# Main_circuit.net
KiCad netlist of a schematic drawn in Altium Designer
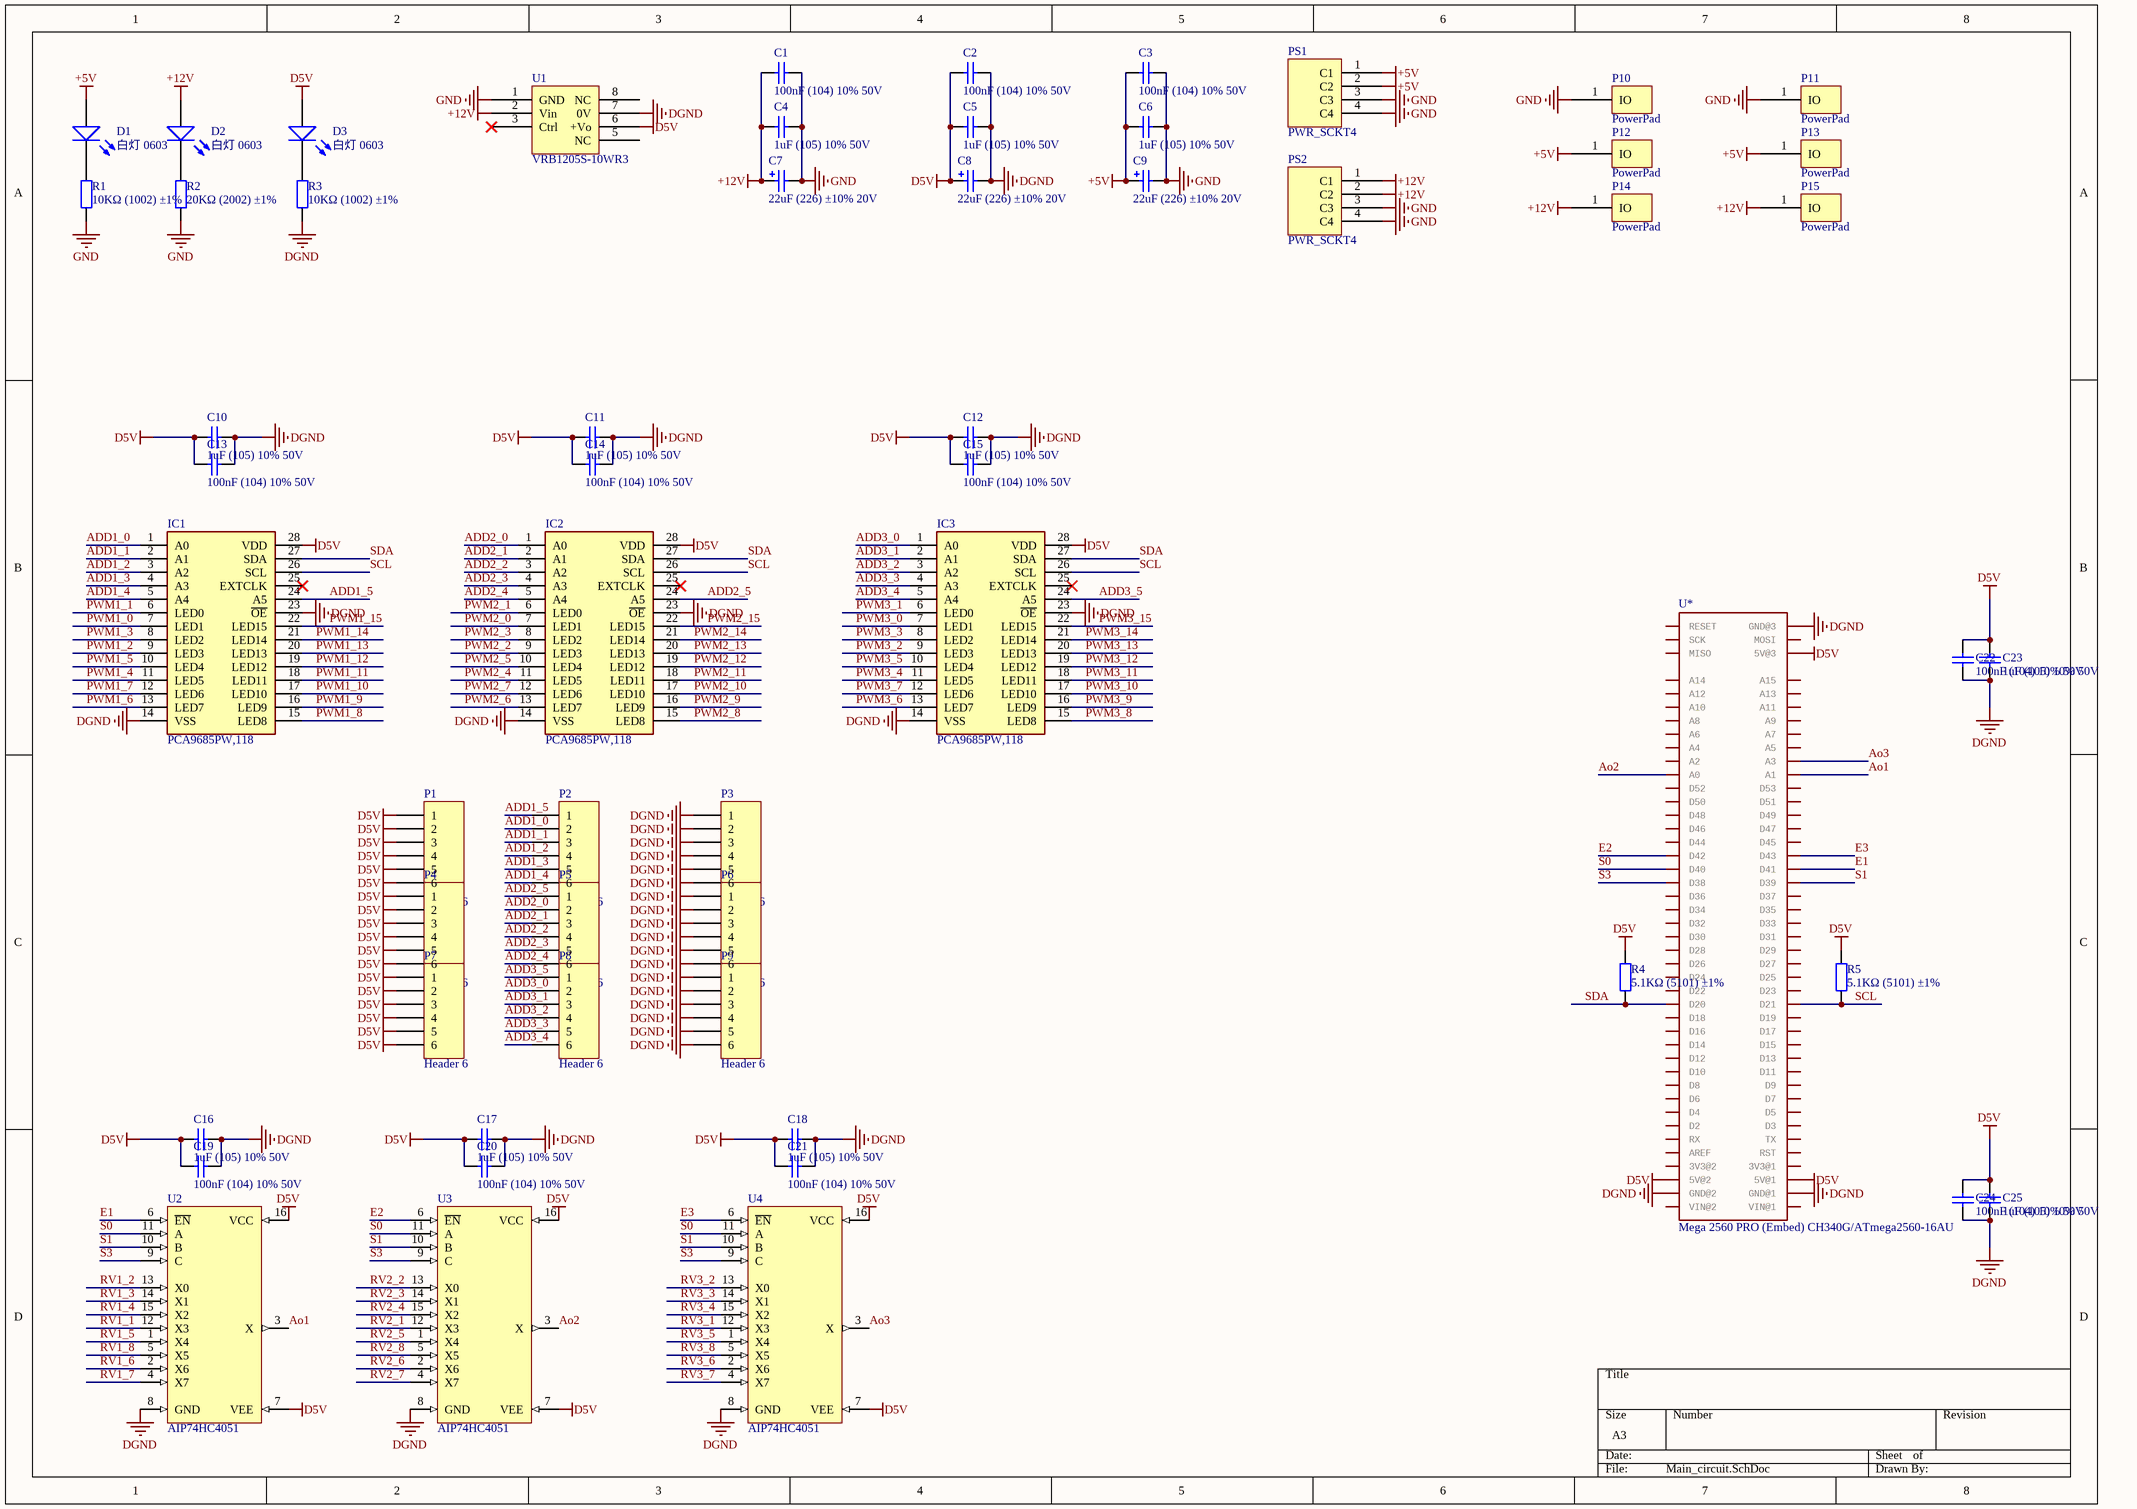
[diagram p0: Main_circuit.SchDoc]

(export (version "E")
  (design (tool "Eeschema 10.0.6"))
  (components
    (comp (ref "C1")
      (value "100nF (104) 10% 50V")
      (footprint "LC-0603_C")
      (description "贴片电容")
      (libsource (lib "Miscellaneous Devices LC") (part "0603 100nF (104) 10% 50V"))
    )
    (comp (ref "C2")
      (value "100nF (104) 10% 50V")
      (footprint "LC-0603_C")
      (description "贴片电容")
      (libsource (lib "Miscellaneous Devices LC") (part "0603 100nF (104) 10% 50V"))
    )
    (comp (ref "C3")
      (value "100nF (104) 10% 50V")
      (footprint "LC-0603_C")
      (description "贴片电容")
      (libsource (lib "Miscellaneous Devices LC") (part "0603 100nF (104) 10% 50V"))
    )
    (comp (ref "C4")
      (value "1uF (105) 10% 50V")
      (footprint "LC-0603_C")
      (description "贴片电容")
      (libsource (lib "Miscellaneous Devices LC") (part "0603 1uF (105) 10% 50V"))
    )
    (comp (ref "C5")
      (value "1uF (105) 10% 50V")
      (footprint "LC-0603_C")
      (description "贴片电容")
      (libsource (lib "Miscellaneous Devices LC") (part "0603 1uF (105) 10% 50V"))
    )
    (comp (ref "C6")
      (value "1uF (105) 10% 50V")
      (footprint "LC-0603_C")
      (description "贴片电容")
      (libsource (lib "Miscellaneous Devices LC") (part "0603 1uF (105) 10% 50V"))
    )
    (comp (ref "C7")
      (value "22uF (226) ±10% 20V")
      (footprint "LC-CASE-B_3528")
      (description "钽电容")
      (libsource (lib "Miscellaneous Devices LC") (part "3216 10uF (106) 10% 16V"))
    )
    (comp (ref "C8")
      (value "22uF (226) ±10% 20V")
      (footprint "LC-CASE-B_3528")
      (description "钽电容")
      (libsource (lib "Miscellaneous Devices LC") (part "3216 10uF (106) 10% 16V"))
    )
    (comp (ref "C9")
      (value "22uF (226) ±10% 20V")
      (footprint "LC-CASE-B_3528")
      (description "钽电容")
      (libsource (lib "Miscellaneous Devices LC") (part "3216 10uF (106) 10% 16V"))
    )
    (comp (ref "C10")
      (value "1uF (105) 10% 50V")
      (footprint "LC-0603_C")
      (description "贴片电容")
      (libsource (lib "Miscellaneous Devices LC") (part "0603 1uF (105) 10% 50V"))
    )
    (comp (ref "C11")
      (value "1uF (105) 10% 50V")
      (footprint "LC-0603_C")
      (description "贴片电容")
      (libsource (lib "Miscellaneous Devices LC") (part "0603 1uF (105) 10% 50V"))
    )
    (comp (ref "C12")
      (value "1uF (105) 10% 50V")
      (footprint "LC-0603_C")
      (description "贴片电容")
      (libsource (lib "Miscellaneous Devices LC") (part "0603 1uF (105) 10% 50V"))
    )
    (comp (ref "C13")
      (value "100nF (104) 10% 50V")
      (footprint "LC-0603_C")
      (description "贴片电容")
      (libsource (lib "Miscellaneous Devices LC") (part "0603 100nF (104) 10% 50V"))
    )
    (comp (ref "C14")
      (value "100nF (104) 10% 50V")
      (footprint "LC-0603_C")
      (description "贴片电容")
      (libsource (lib "Miscellaneous Devices LC") (part "0603 100nF (104) 10% 50V"))
    )
    (comp (ref "C15")
      (value "100nF (104) 10% 50V")
      (footprint "LC-0603_C")
      (description "贴片电容")
      (libsource (lib "Miscellaneous Devices LC") (part "0603 100nF (104) 10% 50V"))
    )
    (comp (ref "C16")
      (value "1uF (105) 10% 50V")
      (footprint "LC-0603_C")
      (description "贴片电容")
      (libsource (lib "Miscellaneous Devices LC") (part "0603 1uF (105) 10% 50V"))
    )
    (comp (ref "C17")
      (value "1uF (105) 10% 50V")
      (footprint "LC-0603_C")
      (description "贴片电容")
      (libsource (lib "Miscellaneous Devices LC") (part "0603 1uF (105) 10% 50V"))
    )
    (comp (ref "C18")
      (value "1uF (105) 10% 50V")
      (footprint "LC-0603_C")
      (description "贴片电容")
      (libsource (lib "Miscellaneous Devices LC") (part "0603 1uF (105) 10% 50V"))
    )
    (comp (ref "C19")
      (value "100nF (104) 10% 50V")
      (footprint "LC-0603_C")
      (description "贴片电容")
      (libsource (lib "Miscellaneous Devices LC") (part "0603 100nF (104) 10% 50V"))
    )
    (comp (ref "C20")
      (value "100nF (104) 10% 50V")
      (footprint "LC-0603_C")
      (description "贴片电容")
      (libsource (lib "Miscellaneous Devices LC") (part "0603 100nF (104) 10% 50V"))
    )
    (comp (ref "C21")
      (value "100nF (104) 10% 50V")
      (footprint "LC-0603_C")
      (description "贴片电容")
      (libsource (lib "Miscellaneous Devices LC") (part "0603 100nF (104) 10% 50V"))
    )
    (comp (ref "C22")
      (value "100nF (104) 10% 50V")
      (footprint "LC-0603_C")
      (description "贴片电容")
      (libsource (lib "Miscellaneous Devices LC") (part "0603 100nF (104) 10% 50V"))
    )
    (comp (ref "C23")
      (value "1uF (105) 10% 50V")
      (footprint "LC-0603_C")
      (description "贴片电容")
      (libsource (lib "Miscellaneous Devices LC") (part "0603 1uF (105) 10% 50V"))
    )
    (comp (ref "C24")
      (value "100nF (104) 10% 50V")
      (footprint "LC-0603_C")
      (description "贴片电容")
      (libsource (lib "Miscellaneous Devices LC") (part "0603 100nF (104) 10% 50V"))
    )
    (comp (ref "C25")
      (value "1uF (105) 10% 50V")
      (footprint "LC-0603_C")
      (description "贴片电容")
      (libsource (lib "Miscellaneous Devices LC") (part "0603 1uF (105) 10% 50V"))
    )
    (comp (ref "D1")
      (value "白灯 0603")
      (footprint "LC-0603_LED_S1")
      (description "发光二极管")
      (libsource (lib "Miscellaneous Devices LC") (part "0603 白灯"))
    )
    (comp (ref "D2")
      (value "白灯 0603")
      (footprint "LC-0603_LED_S1")
      (description "发光二极管")
      (libsource (lib "Miscellaneous Devices LC") (part "0603 白灯"))
    )
    (comp (ref "D3")
      (value "白灯 0603")
      (footprint "LC-0603_LED_S1")
      (description "发光二极管")
      (libsource (lib "Miscellaneous Devices LC") (part "0603 白灯"))
    )
    (comp (ref "IC1")
      (value "PCA9685PW,118")
      (footprint "LC-TSSOP-28")
      (description "Integrated Circuit")
      (libsource (lib "*") (part "PCA9685PW,118"))
    )
    (comp (ref "IC2")
      (value "PCA9685PW,118")
      (footprint "LC-TSSOP-28")
      (description "Integrated Circuit")
      (libsource (lib "*") (part "PCA9685PW,118"))
    )
    (comp (ref "IC3")
      (value "PCA9685PW,118")
      (footprint "LC-TSSOP-28")
      (description "Integrated Circuit")
      (libsource (lib "*") (part "PCA9685PW,118"))
    )
    (comp (ref "P1")
      (value "Header 6")
      (footprint "HDR1X6")
      (description "Header, 6-Pin")
      (fields (field (name "PUBLISHER") "Altium Limited"))
      (libsource (lib "Miscellaneous Connectors") (part "Header 6"))
    )
    (comp (ref "P2")
      (value "Header 6")
      (footprint "HDR1X6")
      (description "Header, 6-Pin")
      (fields (field (name "PUBLISHER") "Altium Limited"))
      (libsource (lib "Miscellaneous Connectors") (part "Header 6"))
    )
    (comp (ref "P3")
      (value "Header 6")
      (footprint "HDR1X6")
      (description "Header, 6-Pin")
      (fields (field (name "PUBLISHER") "Altium Limited"))
      (libsource (lib "Miscellaneous Connectors") (part "Header 6"))
    )
    (comp (ref "P4")
      (value "Header 6")
      (footprint "HDR1X6")
      (description "Header, 6-Pin")
      (fields (field (name "PUBLISHER") "Altium Limited"))
      (libsource (lib "Miscellaneous Connectors") (part "Header 6"))
    )
    (comp (ref "P5")
      (value "Header 6")
      (footprint "HDR1X6")
      (description "Header, 6-Pin")
      (fields (field (name "PUBLISHER") "Altium Limited"))
      (libsource (lib "Miscellaneous Connectors") (part "Header 6"))
    )
    (comp (ref "P6")
      (value "Header 6")
      (footprint "HDR1X6")
      (description "Header, 6-Pin")
      (fields (field (name "PUBLISHER") "Altium Limited"))
      (libsource (lib "Miscellaneous Connectors") (part "Header 6"))
    )
    (comp (ref "P7")
      (value "Header 6")
      (footprint "HDR1X6")
      (description "Header, 6-Pin")
      (fields (field (name "PUBLISHER") "Altium Limited"))
      (libsource (lib "Miscellaneous Connectors") (part "Header 6"))
    )
    (comp (ref "P8")
      (value "Header 6")
      (footprint "HDR1X6")
      (description "Header, 6-Pin")
      (fields (field (name "PUBLISHER") "Altium Limited"))
      (libsource (lib "Miscellaneous Connectors") (part "Header 6"))
    )
    (comp (ref "P9")
      (value "Header 6")
      (footprint "HDR1X6")
      (description "Header, 6-Pin")
      (fields (field (name "PUBLISHER") "Altium Limited"))
      (libsource (lib "Miscellaneous Connectors") (part "Header 6"))
    )
    (comp (ref "P10") (value "PowerPad") (footprint "PowerPad") (libsource (lib "Schlib1") (part "PowerPad")))
    (comp (ref "P11") (value "PowerPad") (footprint "PowerPad") (libsource (lib "Schlib1") (part "PowerPad")))
    (comp (ref "P12") (value "PowerPad") (footprint "PowerPad") (libsource (lib "Schlib1") (part "PowerPad")))
    (comp (ref "P13") (value "PowerPad") (footprint "PowerPad") (libsource (lib "Schlib1") (part "PowerPad")))
    (comp (ref "P14") (value "PowerPad") (footprint "PowerPad") (libsource (lib "Schlib1") (part "PowerPad")))
    (comp (ref "P15") (value "PowerPad") (footprint "PowerPad") (libsource (lib "Schlib1") (part "PowerPad")))
    (comp (ref "PS1")
      (value "PWR_SCKT4")
      (footprint "PWR_SCKT_4P3.81")
      (description "POWER SOCKET")
      (libsource (lib "PG_lib") (part "POWER_SOCKET4"))
    )
    (comp (ref "PS2")
      (value "PWR_SCKT4")
      (footprint "PWR_SCKT_4P3.81")
      (description "POWER SOCKET")
      (libsource (lib "PG_lib") (part "POWER_SOCKET4"))
    )
    (comp (ref "R1")
      (value "10KΩ (1002) ±1%")
      (footprint "LC-0603_R")
      (description "贴片电阻")
      (libsource (lib "Miscellaneous Devices LC") (part "0603 10KΩ (1002) 1%"))
    )
    (comp (ref "R2")
      (value "20KΩ (2002) ±1%")
      (footprint "LC-0603_R")
      (description "贴片电阻")
      (libsource (lib "Miscellaneous Devices LC") (part "0603 20KΩ (2002) 1%"))
    )
    (comp (ref "R3")
      (value "10KΩ (1002) ±1%")
      (footprint "LC-0603_R")
      (description "贴片电阻")
      (libsource (lib "Miscellaneous Devices LC") (part "0603 10KΩ (1002) 1%"))
    )
    (comp (ref "R4")
      (value "5.1KΩ (5101) ±1%")
      (footprint "LC-0603_R")
      (description "贴片电阻")
      (libsource (lib "Miscellaneous Devices LC") (part "0603 5.1KΩ (5101) 1%"))
    )
    (comp (ref "R5")
      (value "5.1KΩ (5101) ±1%")
      (footprint "LC-0603_R")
      (description "贴片电阻")
      (libsource (lib "Miscellaneous Devices LC") (part "0603 5.1KΩ (5101) 1%"))
    )
    (comp (ref "U*")
      (value "Mega 2560 PRO (Embed) CH340G/ATmega2560-16AU")
      (footprint "Mega 2560 PRO (Embed)")
      (libsource (lib "Mega2560Pro") (part "Mega 2560 PRO (Embed)"))
    )
    (comp (ref "U1")
      (value "VRB1205S-10WR3")
      (footprint "VRB1205S-10WR3")
      (libsource (lib "Schlib1") (part "VRB1205S-10WR3"))
    )
    (comp (ref "U2")
      (value "AIP74HC4051")
      (footprint "LC-SOP-16_150mil")
      (description "4000系列逻辑芯片")
      (libsource (lib "Miscellaneous Devices LC") (part "CD4051BM96"))
    )
    (comp (ref "U3")
      (value "AIP74HC4051")
      (footprint "LC-SOP-16_150mil")
      (description "4000系列逻辑芯片")
      (libsource (lib "Miscellaneous Devices LC") (part "CD4051BM96"))
    )
    (comp (ref "U4")
      (value "AIP74HC4051")
      (footprint "LC-SOP-16_150mil")
      (description "4000系列逻辑芯片")
      (libsource (lib "Miscellaneous Devices LC") (part "CD4051BM96"))
    )
  )
  (nets
    (net (code "1") (name "+5V") (class "Default")
      (node (ref "C3") (pin "2") (pinfunction "2_2") (pintype "passive"))
      (node (ref "C6") (pin "2") (pinfunction "2_2") (pintype "passive"))
      (node (ref "C9") (pin "1") (pinfunction "1_1") (pintype "passive"))
      (node (ref "D1") (pin "A") (pinfunction "A_A") (pintype "passive"))
      (node (ref "P12") (pin "1") (pinfunction "IO_1") (pintype "passive"))
      (node (ref "P13") (pin "1") (pinfunction "IO_1") (pintype "passive"))
      (node (ref "PS1") (pin "1") (pinfunction "C1_1") (pintype "passive"))
      (node (ref "PS1") (pin "2") (pinfunction "C2_2") (pintype "passive"))
    )
    (net (code "2") (name "+12V") (class "Default")
      (node (ref "C1") (pin "2") (pinfunction "2_2") (pintype "passive"))
      (node (ref "C4") (pin "2") (pinfunction "2_2") (pintype "passive"))
      (node (ref "C7") (pin "1") (pinfunction "1_1") (pintype "passive"))
      (node (ref "D2") (pin "A") (pinfunction "A_A") (pintype "passive"))
      (node (ref "P14") (pin "1") (pinfunction "IO_1") (pintype "passive"))
      (node (ref "P15") (pin "1") (pinfunction "IO_1") (pintype "passive"))
      (node (ref "PS2") (pin "1") (pinfunction "C1_1") (pintype "passive"))
      (node (ref "PS2") (pin "2") (pinfunction "C2_2") (pintype "passive"))
      (node (ref "U1") (pin "2") (pinfunction "Vin_2") (pintype "passive"))
    )
    (net (code "3") (name "/ADD1_0") (class "Default")
      (node (ref "IC1") (pin "1") (pinfunction "A0_1") (pintype "passive"))
      (node (ref "P2") (pin "2") (pinfunction "2_2") (pintype "passive"))
    )
    (net (code "4") (name "/ADD1_1") (class "Default")
      (node (ref "IC1") (pin "2") (pinfunction "A1_2") (pintype "passive"))
      (node (ref "P2") (pin "3") (pinfunction "3_3") (pintype "passive"))
    )
    (net (code "5") (name "/ADD1_2") (class "Default")
      (node (ref "IC1") (pin "3") (pinfunction "A2_3") (pintype "passive"))
      (node (ref "P2") (pin "4") (pinfunction "4_4") (pintype "passive"))
    )
    (net (code "6") (name "/ADD1_3") (class "Default")
      (node (ref "IC1") (pin "4") (pinfunction "A3_4") (pintype "passive"))
      (node (ref "P2") (pin "5") (pinfunction "5_5") (pintype "passive"))
    )
    (net (code "7") (name "/ADD1_4") (class "Default")
      (node (ref "IC1") (pin "5") (pinfunction "A4_5") (pintype "passive"))
      (node (ref "P2") (pin "6") (pinfunction "6_6") (pintype "passive"))
    )
    (net (code "8") (name "/ADD1_5") (class "Default")
      (node (ref "IC1") (pin "24") (pinfunction "A5_24") (pintype "passive"))
      (node (ref "P2") (pin "1") (pinfunction "1_1") (pintype "passive"))
    )
    (net (code "9") (name "/ADD2_0") (class "Default")
      (node (ref "IC2") (pin "1") (pinfunction "A0_1") (pintype "passive"))
      (node (ref "P5") (pin "2") (pinfunction "2_2") (pintype "passive"))
    )
    (net (code "10") (name "/ADD2_1") (class "Default")
      (node (ref "IC2") (pin "2") (pinfunction "A1_2") (pintype "passive"))
      (node (ref "P5") (pin "3") (pinfunction "3_3") (pintype "passive"))
    )
    (net (code "11") (name "/ADD2_2") (class "Default")
      (node (ref "IC2") (pin "3") (pinfunction "A2_3") (pintype "passive"))
      (node (ref "P5") (pin "4") (pinfunction "4_4") (pintype "passive"))
    )
    (net (code "12") (name "/ADD2_3") (class "Default")
      (node (ref "IC2") (pin "4") (pinfunction "A3_4") (pintype "passive"))
      (node (ref "P5") (pin "5") (pinfunction "5_5") (pintype "passive"))
    )
    (net (code "13") (name "/ADD2_4") (class "Default")
      (node (ref "IC2") (pin "5") (pinfunction "A4_5") (pintype "passive"))
      (node (ref "P5") (pin "6") (pinfunction "6_6") (pintype "passive"))
    )
    (net (code "14") (name "/ADD2_5") (class "Default")
      (node (ref "IC2") (pin "24") (pinfunction "A5_24") (pintype "passive"))
      (node (ref "P5") (pin "1") (pinfunction "1_1") (pintype "passive"))
    )
    (net (code "15") (name "/ADD3_0") (class "Default")
      (node (ref "IC3") (pin "1") (pinfunction "A0_1") (pintype "passive"))
      (node (ref "P8") (pin "2") (pinfunction "2_2") (pintype "passive"))
    )
    (net (code "16") (name "/ADD3_1") (class "Default")
      (node (ref "IC3") (pin "2") (pinfunction "A1_2") (pintype "passive"))
      (node (ref "P8") (pin "3") (pinfunction "3_3") (pintype "passive"))
    )
    (net (code "17") (name "/ADD3_2") (class "Default")
      (node (ref "IC3") (pin "3") (pinfunction "A2_3") (pintype "passive"))
      (node (ref "P8") (pin "4") (pinfunction "4_4") (pintype "passive"))
    )
    (net (code "18") (name "/ADD3_3") (class "Default")
      (node (ref "IC3") (pin "4") (pinfunction "A3_4") (pintype "passive"))
      (node (ref "P8") (pin "5") (pinfunction "5_5") (pintype "passive"))
    )
    (net (code "19") (name "/ADD3_4") (class "Default")
      (node (ref "IC3") (pin "5") (pinfunction "A4_5") (pintype "passive"))
      (node (ref "P8") (pin "6") (pinfunction "6_6") (pintype "passive"))
    )
    (net (code "20") (name "/ADD3_5") (class "Default")
      (node (ref "IC3") (pin "24") (pinfunction "A5_24") (pintype "passive"))
      (node (ref "P8") (pin "1") (pinfunction "1_1") (pintype "passive"))
    )
    (net (code "21") (name "/Ao1") (class "Default")
      (node (ref "U*") (pin "A1") (pinfunction "A1_A1") (pintype "bidirectional"))
      (node (ref "U2") (pin "3") (pinfunction "X_3") (pintype "output"))
    )
    (net (code "22") (name "/Ao2") (class "Default")
      (node (ref "U*") (pin "A0") (pinfunction "A0_A0") (pintype "bidirectional"))
      (node (ref "U3") (pin "3") (pinfunction "X_3") (pintype "output"))
    )
    (net (code "23") (name "/Ao3") (class "Default")
      (node (ref "U*") (pin "A3") (pinfunction "A3_A3") (pintype "bidirectional"))
      (node (ref "U4") (pin "3") (pinfunction "X_3") (pintype "output"))
    )
    (net (code "24") (name "/E1") (class "Default")
      (node (ref "U*") (pin "D41") (pinfunction "D41_D41") (pintype "bidirectional"))
      (node (ref "U2") (pin "6") (pinfunction "~{EN}_6") (pintype "input"))
    )
    (net (code "25") (name "/E2") (class "Default")
      (node (ref "U*") (pin "D42") (pinfunction "D42_D42") (pintype "bidirectional"))
      (node (ref "U3") (pin "6") (pinfunction "~{EN}_6") (pintype "input"))
    )
    (net (code "26") (name "/E3") (class "Default")
      (node (ref "U*") (pin "D43") (pinfunction "D43_D43") (pintype "bidirectional"))
      (node (ref "U4") (pin "6") (pinfunction "~{EN}_6") (pintype "input"))
    )
    (net (code "27") (name "/PWM1_0") (class "Default")
      (node (ref "IC1") (pin "7") (pinfunction "LED1_7") (pintype "passive"))
    )
    (net (code "28") (name "/PWM1_1") (class "Default")
      (node (ref "IC1") (pin "6") (pinfunction "LED0_6") (pintype "passive"))
    )
    (net (code "29") (name "/PWM1_2") (class "Default")
      (node (ref "IC1") (pin "9") (pinfunction "LED3_9") (pintype "passive"))
    )
    (net (code "30") (name "/PWM1_3") (class "Default")
      (node (ref "IC1") (pin "8") (pinfunction "LED2_8") (pintype "passive"))
    )
    (net (code "31") (name "/PWM1_4") (class "Default")
      (node (ref "IC1") (pin "11") (pinfunction "LED5_11") (pintype "passive"))
    )
    (net (code "32") (name "/PWM1_5") (class "Default")
      (node (ref "IC1") (pin "10") (pinfunction "LED4_10") (pintype "passive"))
    )
    (net (code "33") (name "/PWM1_6") (class "Default")
      (node (ref "IC1") (pin "13") (pinfunction "LED7_13") (pintype "passive"))
    )
    (net (code "34") (name "/PWM1_7") (class "Default")
      (node (ref "IC1") (pin "12") (pinfunction "LED6_12") (pintype "passive"))
    )
    (net (code "35") (name "/PWM1_8") (class "Default")
      (node (ref "IC1") (pin "15") (pinfunction "LED8_15") (pintype "passive"))
    )
    (net (code "36") (name "/PWM1_9") (class "Default")
      (node (ref "IC1") (pin "16") (pinfunction "LED9_16") (pintype "passive"))
    )
    (net (code "37") (name "/PWM1_10") (class "Default")
      (node (ref "IC1") (pin "17") (pinfunction "LED10_17") (pintype "passive"))
    )
    (net (code "38") (name "/PWM1_11") (class "Default")
      (node (ref "IC1") (pin "18") (pinfunction "LED11_18") (pintype "passive"))
    )
    (net (code "39") (name "/PWM1_12") (class "Default")
      (node (ref "IC1") (pin "19") (pinfunction "LED12_19") (pintype "passive"))
    )
    (net (code "40") (name "/PWM1_13") (class "Default")
      (node (ref "IC1") (pin "20") (pinfunction "LED13_20") (pintype "passive"))
    )
    (net (code "41") (name "/PWM1_14") (class "Default")
      (node (ref "IC1") (pin "21") (pinfunction "LED14_21") (pintype "passive"))
    )
    (net (code "42") (name "/PWM1_15") (class "Default")
      (node (ref "IC1") (pin "22") (pinfunction "LED15_22") (pintype "passive"))
    )
    (net (code "43") (name "/PWM2_0") (class "Default")
      (node (ref "IC2") (pin "7") (pinfunction "LED1_7") (pintype "passive"))
    )
    (net (code "44") (name "/PWM2_1") (class "Default")
      (node (ref "IC2") (pin "6") (pinfunction "LED0_6") (pintype "passive"))
    )
    (net (code "45") (name "/PWM2_2") (class "Default")
      (node (ref "IC2") (pin "9") (pinfunction "LED3_9") (pintype "passive"))
    )
    (net (code "46") (name "/PWM2_3") (class "Default")
      (node (ref "IC2") (pin "8") (pinfunction "LED2_8") (pintype "passive"))
    )
    (net (code "47") (name "/PWM2_4") (class "Default")
      (node (ref "IC2") (pin "11") (pinfunction "LED5_11") (pintype "passive"))
    )
    (net (code "48") (name "/PWM2_5") (class "Default")
      (node (ref "IC2") (pin "10") (pinfunction "LED4_10") (pintype "passive"))
    )
    (net (code "49") (name "/PWM2_6") (class "Default")
      (node (ref "IC2") (pin "13") (pinfunction "LED7_13") (pintype "passive"))
    )
    (net (code "50") (name "/PWM2_7") (class "Default")
      (node (ref "IC2") (pin "12") (pinfunction "LED6_12") (pintype "passive"))
    )
    (net (code "51") (name "/PWM2_8") (class "Default")
      (node (ref "IC2") (pin "15") (pinfunction "LED8_15") (pintype "passive"))
    )
    (net (code "52") (name "/PWM2_9") (class "Default")
      (node (ref "IC2") (pin "16") (pinfunction "LED9_16") (pintype "passive"))
    )
    (net (code "53") (name "/PWM2_10") (class "Default")
      (node (ref "IC2") (pin "17") (pinfunction "LED10_17") (pintype "passive"))
    )
    (net (code "54") (name "/PWM2_11") (class "Default")
      (node (ref "IC2") (pin "18") (pinfunction "LED11_18") (pintype "passive"))
    )
    (net (code "55") (name "/PWM2_12") (class "Default")
      (node (ref "IC2") (pin "19") (pinfunction "LED12_19") (pintype "passive"))
    )
    (net (code "56") (name "/PWM2_13") (class "Default")
      (node (ref "IC2") (pin "20") (pinfunction "LED13_20") (pintype "passive"))
    )
    (net (code "57") (name "/PWM2_14") (class "Default")
      (node (ref "IC2") (pin "21") (pinfunction "LED14_21") (pintype "passive"))
    )
    (net (code "58") (name "/PWM2_15") (class "Default")
      (node (ref "IC2") (pin "22") (pinfunction "LED15_22") (pintype "passive"))
    )
    (net (code "59") (name "/PWM3_0") (class "Default")
      (node (ref "IC3") (pin "7") (pinfunction "LED1_7") (pintype "passive"))
    )
    (net (code "60") (name "/PWM3_1") (class "Default")
      (node (ref "IC3") (pin "6") (pinfunction "LED0_6") (pintype "passive"))
    )
    (net (code "61") (name "/PWM3_2") (class "Default")
      (node (ref "IC3") (pin "9") (pinfunction "LED3_9") (pintype "passive"))
    )
    (net (code "62") (name "/PWM3_3") (class "Default")
      (node (ref "IC3") (pin "8") (pinfunction "LED2_8") (pintype "passive"))
    )
    (net (code "63") (name "/PWM3_4") (class "Default")
      (node (ref "IC3") (pin "11") (pinfunction "LED5_11") (pintype "passive"))
    )
    (net (code "64") (name "/PWM3_5") (class "Default")
      (node (ref "IC3") (pin "10") (pinfunction "LED4_10") (pintype "passive"))
    )
    (net (code "65") (name "/PWM3_6") (class "Default")
      (node (ref "IC3") (pin "13") (pinfunction "LED7_13") (pintype "passive"))
    )
    (net (code "66") (name "/PWM3_7") (class "Default")
      (node (ref "IC3") (pin "12") (pinfunction "LED6_12") (pintype "passive"))
    )
    (net (code "67") (name "/PWM3_8") (class "Default")
      (node (ref "IC3") (pin "15") (pinfunction "LED8_15") (pintype "passive"))
    )
    (net (code "68") (name "/PWM3_9") (class "Default")
      (node (ref "IC3") (pin "16") (pinfunction "LED9_16") (pintype "passive"))
    )
    (net (code "69") (name "/PWM3_10") (class "Default")
      (node (ref "IC3") (pin "17") (pinfunction "LED10_17") (pintype "passive"))
    )
    (net (code "70") (name "/PWM3_11") (class "Default")
      (node (ref "IC3") (pin "18") (pinfunction "LED11_18") (pintype "passive"))
    )
    (net (code "71") (name "/PWM3_12") (class "Default")
      (node (ref "IC3") (pin "19") (pinfunction "LED12_19") (pintype "passive"))
    )
    (net (code "72") (name "/PWM3_13") (class "Default")
      (node (ref "IC3") (pin "20") (pinfunction "LED13_20") (pintype "passive"))
    )
    (net (code "73") (name "/PWM3_14") (class "Default")
      (node (ref "IC3") (pin "21") (pinfunction "LED14_21") (pintype "passive"))
    )
    (net (code "74") (name "/PWM3_15") (class "Default")
      (node (ref "IC3") (pin "22") (pinfunction "LED15_22") (pintype "passive"))
    )
    (net (code "75") (name "/RV1_1") (class "Default")
      (node (ref "U2") (pin "12") (pinfunction "X3_12") (pintype "input"))
    )
    (net (code "76") (name "/RV1_2") (class "Default")
      (node (ref "U2") (pin "13") (pinfunction "X0_13") (pintype "input"))
    )
    (net (code "77") (name "/RV1_3") (class "Default")
      (node (ref "U2") (pin "14") (pinfunction "X1_14") (pintype "input"))
    )
    (net (code "78") (name "/RV1_4") (class "Default")
      (node (ref "U2") (pin "15") (pinfunction "X2_15") (pintype "input"))
    )
    (net (code "79") (name "/RV1_5") (class "Default")
      (node (ref "U2") (pin "1") (pinfunction "X4_1") (pintype "input"))
    )
    (net (code "80") (name "/RV1_6") (class "Default")
      (node (ref "U2") (pin "2") (pinfunction "X6_2") (pintype "input"))
    )
    (net (code "81") (name "/RV1_7") (class "Default")
      (node (ref "U2") (pin "4") (pinfunction "X7_4") (pintype "input"))
    )
    (net (code "82") (name "/RV1_8") (class "Default")
      (node (ref "U2") (pin "5") (pinfunction "X5_5") (pintype "input"))
    )
    (net (code "83") (name "/RV2_1") (class "Default")
      (node (ref "U3") (pin "12") (pinfunction "X3_12") (pintype "input"))
    )
    (net (code "84") (name "/RV2_2") (class "Default")
      (node (ref "U3") (pin "13") (pinfunction "X0_13") (pintype "input"))
    )
    (net (code "85") (name "/RV2_3") (class "Default")
      (node (ref "U3") (pin "14") (pinfunction "X1_14") (pintype "input"))
    )
    (net (code "86") (name "/RV2_4") (class "Default")
      (node (ref "U3") (pin "15") (pinfunction "X2_15") (pintype "input"))
    )
    (net (code "87") (name "/RV2_5") (class "Default")
      (node (ref "U3") (pin "1") (pinfunction "X4_1") (pintype "input"))
    )
    (net (code "88") (name "/RV2_6") (class "Default")
      (node (ref "U3") (pin "2") (pinfunction "X6_2") (pintype "input"))
    )
    (net (code "89") (name "/RV2_7") (class "Default")
      (node (ref "U3") (pin "4") (pinfunction "X7_4") (pintype "input"))
    )
    (net (code "90") (name "/RV2_8") (class "Default")
      (node (ref "U3") (pin "5") (pinfunction "X5_5") (pintype "input"))
    )
    (net (code "91") (name "/RV3_1") (class "Default")
      (node (ref "U4") (pin "12") (pinfunction "X3_12") (pintype "input"))
    )
    (net (code "92") (name "/RV3_2") (class "Default")
      (node (ref "U4") (pin "13") (pinfunction "X0_13") (pintype "input"))
    )
    (net (code "93") (name "/RV3_3") (class "Default")
      (node (ref "U4") (pin "14") (pinfunction "X1_14") (pintype "input"))
    )
    (net (code "94") (name "/RV3_4") (class "Default")
      (node (ref "U4") (pin "15") (pinfunction "X2_15") (pintype "input"))
    )
    (net (code "95") (name "/RV3_5") (class "Default")
      (node (ref "U4") (pin "1") (pinfunction "X4_1") (pintype "input"))
    )
    (net (code "96") (name "/RV3_6") (class "Default")
      (node (ref "U4") (pin "2") (pinfunction "X6_2") (pintype "input"))
    )
    (net (code "97") (name "/RV3_7") (class "Default")
      (node (ref "U4") (pin "4") (pinfunction "X7_4") (pintype "input"))
    )
    (net (code "98") (name "/RV3_8") (class "Default")
      (node (ref "U4") (pin "5") (pinfunction "X5_5") (pintype "input"))
    )
    (net (code "99") (name "/S0") (class "Default")
      (node (ref "U*") (pin "D40") (pinfunction "D40_D40") (pintype "bidirectional"))
      (node (ref "U2") (pin "11") (pinfunction "A_11") (pintype "input"))
      (node (ref "U3") (pin "11") (pinfunction "A_11") (pintype "input"))
      (node (ref "U4") (pin "11") (pinfunction "A_11") (pintype "input"))
    )
    (net (code "100") (name "/S1") (class "Default")
      (node (ref "U*") (pin "D39") (pinfunction "D39_D39") (pintype "bidirectional"))
      (node (ref "U2") (pin "10") (pinfunction "B_10") (pintype "input"))
      (node (ref "U3") (pin "10") (pinfunction "B_10") (pintype "input"))
      (node (ref "U4") (pin "10") (pinfunction "B_10") (pintype "input"))
    )
    (net (code "101") (name "/S3") (class "Default")
      (node (ref "U*") (pin "D38") (pinfunction "D38_D38") (pintype "bidirectional"))
      (node (ref "U2") (pin "9") (pinfunction "C_9") (pintype "input"))
      (node (ref "U3") (pin "9") (pinfunction "C_9") (pintype "input"))
      (node (ref "U4") (pin "9") (pinfunction "C_9") (pintype "input"))
    )
    (net (code "102") (name "/SCL") (class "Default")
      (node (ref "IC1") (pin "26") (pinfunction "SCL_26") (pintype "passive"))
      (node (ref "IC2") (pin "26") (pinfunction "SCL_26") (pintype "passive"))
      (node (ref "IC3") (pin "26") (pinfunction "SCL_26") (pintype "passive"))
      (node (ref "R5") (pin "1") (pinfunction "1_1") (pintype "passive"))
      (node (ref "U*") (pin "D21") (pinfunction "D21_D21") (pintype "bidirectional"))
    )
    (net (code "103") (name "/SDA") (class "Default")
      (node (ref "IC1") (pin "27") (pinfunction "SDA_27") (pintype "passive"))
      (node (ref "IC2") (pin "27") (pinfunction "SDA_27") (pintype "passive"))
      (node (ref "IC3") (pin "27") (pinfunction "SDA_27") (pintype "passive"))
      (node (ref "R4") (pin "1") (pinfunction "1_1") (pintype "passive"))
      (node (ref "U*") (pin "D20") (pinfunction "D20_D20") (pintype "bidirectional"))
    )
    (net (code "104") (name "D5V") (class "Default")
      (node (ref "C10") (pin "1") (pinfunction "1_1") (pintype "passive"))
      (node (ref "C11") (pin "1") (pinfunction "1_1") (pintype "passive"))
      (node (ref "C12") (pin "1") (pinfunction "1_1") (pintype "passive"))
      (node (ref "C13") (pin "1") (pinfunction "1_1") (pintype "passive"))
      (node (ref "C14") (pin "1") (pinfunction "1_1") (pintype "passive"))
      (node (ref "C15") (pin "1") (pinfunction "1_1") (pintype "passive"))
      (node (ref "C16") (pin "1") (pinfunction "1_1") (pintype "passive"))
      (node (ref "C17") (pin "1") (pinfunction "1_1") (pintype "passive"))
      (node (ref "C18") (pin "1") (pinfunction "1_1") (pintype "passive"))
      (node (ref "C19") (pin "1") (pinfunction "1_1") (pintype "passive"))
      (node (ref "C2") (pin "2") (pinfunction "2_2") (pintype "passive"))
      (node (ref "C20") (pin "1") (pinfunction "1_1") (pintype "passive"))
      (node (ref "C21") (pin "1") (pinfunction "1_1") (pintype "passive"))
      (node (ref "C22") (pin "1") (pinfunction "1_1") (pintype "passive"))
      (node (ref "C23") (pin "1") (pinfunction "1_1") (pintype "passive"))
      (node (ref "C24") (pin "1") (pinfunction "1_1") (pintype "passive"))
      (node (ref "C25") (pin "1") (pinfunction "1_1") (pintype "passive"))
      (node (ref "C5") (pin "2") (pinfunction "2_2") (pintype "passive"))
      (node (ref "C8") (pin "1") (pinfunction "1_1") (pintype "passive"))
      (node (ref "D3") (pin "A") (pinfunction "A_A") (pintype "passive"))
      (node (ref "IC1") (pin "28") (pinfunction "VDD_28") (pintype "passive"))
      (node (ref "IC2") (pin "28") (pinfunction "VDD_28") (pintype "passive"))
      (node (ref "IC3") (pin "28") (pinfunction "VDD_28") (pintype "passive"))
      (node (ref "P1") (pin "1") (pinfunction "1_1") (pintype "passive"))
      (node (ref "P1") (pin "2") (pinfunction "2_2") (pintype "passive"))
      (node (ref "P1") (pin "3") (pinfunction "3_3") (pintype "passive"))
      (node (ref "P1") (pin "4") (pinfunction "4_4") (pintype "passive"))
      (node (ref "P1") (pin "5") (pinfunction "5_5") (pintype "passive"))
      (node (ref "P1") (pin "6") (pinfunction "6_6") (pintype "passive"))
      (node (ref "P4") (pin "1") (pinfunction "1_1") (pintype "passive"))
      (node (ref "P4") (pin "2") (pinfunction "2_2") (pintype "passive"))
      (node (ref "P4") (pin "3") (pinfunction "3_3") (pintype "passive"))
      (node (ref "P4") (pin "4") (pinfunction "4_4") (pintype "passive"))
      (node (ref "P4") (pin "5") (pinfunction "5_5") (pintype "passive"))
      (node (ref "P4") (pin "6") (pinfunction "6_6") (pintype "passive"))
      (node (ref "P7") (pin "1") (pinfunction "1_1") (pintype "passive"))
      (node (ref "P7") (pin "2") (pinfunction "2_2") (pintype "passive"))
      (node (ref "P7") (pin "3") (pinfunction "3_3") (pintype "passive"))
      (node (ref "P7") (pin "4") (pinfunction "4_4") (pintype "passive"))
      (node (ref "P7") (pin "5") (pinfunction "5_5") (pintype "passive"))
      (node (ref "P7") (pin "6") (pinfunction "6_6") (pintype "passive"))
      (node (ref "R4") (pin "2") (pinfunction "2_2") (pintype "passive"))
      (node (ref "R5") (pin "2") (pinfunction "2_2") (pintype "passive"))
      (node (ref "U*") (pin "5V@1") (pinfunction "5V@1_5V@1") (pintype "bidirectional"))
      (node (ref "U*") (pin "5V@2") (pinfunction "5V@2_5V@2") (pintype "bidirectional"))
      (node (ref "U*") (pin "5V@3") (pinfunction "5V@3_5V@3") (pintype "bidirectional"))
      (node (ref "U1") (pin "6") (pinfunction "+Vo_6") (pintype "passive"))
      (node (ref "U2") (pin "16") (pinfunction "VCC_16") (pintype "input"))
      (node (ref "U2") (pin "7") (pinfunction "VEE_7") (pintype "input"))
      (node (ref "U3") (pin "16") (pinfunction "VCC_16") (pintype "input"))
      (node (ref "U3") (pin "7") (pinfunction "VEE_7") (pintype "input"))
      (node (ref "U4") (pin "16") (pinfunction "VCC_16") (pintype "input"))
      (node (ref "U4") (pin "7") (pinfunction "VEE_7") (pintype "input"))
    )
    (net (code "105") (name "DGND") (class "Default")
      (node (ref "C10") (pin "2") (pinfunction "2_2") (pintype "passive"))
      (node (ref "C11") (pin "2") (pinfunction "2_2") (pintype "passive"))
      (node (ref "C12") (pin "2") (pinfunction "2_2") (pintype "passive"))
      (node (ref "C13") (pin "2") (pinfunction "2_2") (pintype "passive"))
      (node (ref "C14") (pin "2") (pinfunction "2_2") (pintype "passive"))
      (node (ref "C15") (pin "2") (pinfunction "2_2") (pintype "passive"))
      (node (ref "C16") (pin "2") (pinfunction "2_2") (pintype "passive"))
      (node (ref "C17") (pin "2") (pinfunction "2_2") (pintype "passive"))
      (node (ref "C18") (pin "2") (pinfunction "2_2") (pintype "passive"))
      (node (ref "C19") (pin "2") (pinfunction "2_2") (pintype "passive"))
      (node (ref "C2") (pin "1") (pinfunction "1_1") (pintype "passive"))
      (node (ref "C20") (pin "2") (pinfunction "2_2") (pintype "passive"))
      (node (ref "C21") (pin "2") (pinfunction "2_2") (pintype "passive"))
      (node (ref "C22") (pin "2") (pinfunction "2_2") (pintype "passive"))
      (node (ref "C23") (pin "2") (pinfunction "2_2") (pintype "passive"))
      (node (ref "C24") (pin "2") (pinfunction "2_2") (pintype "passive"))
      (node (ref "C25") (pin "2") (pinfunction "2_2") (pintype "passive"))
      (node (ref "C5") (pin "1") (pinfunction "1_1") (pintype "passive"))
      (node (ref "C8") (pin "2") (pinfunction "2_2") (pintype "passive"))
      (node (ref "IC1") (pin "14") (pinfunction "VSS_14") (pintype "passive"))
      (node (ref "IC1") (pin "23") (pinfunction "~{OE}_23") (pintype "passive"))
      (node (ref "IC2") (pin "14") (pinfunction "VSS_14") (pintype "passive"))
      (node (ref "IC2") (pin "23") (pinfunction "~{OE}_23") (pintype "passive"))
      (node (ref "IC3") (pin "14") (pinfunction "VSS_14") (pintype "passive"))
      (node (ref "IC3") (pin "23") (pinfunction "~{OE}_23") (pintype "passive"))
      (node (ref "P3") (pin "1") (pinfunction "1_1") (pintype "passive"))
      (node (ref "P3") (pin "2") (pinfunction "2_2") (pintype "passive"))
      (node (ref "P3") (pin "3") (pinfunction "3_3") (pintype "passive"))
      (node (ref "P3") (pin "4") (pinfunction "4_4") (pintype "passive"))
      (node (ref "P3") (pin "5") (pinfunction "5_5") (pintype "passive"))
      (node (ref "P3") (pin "6") (pinfunction "6_6") (pintype "passive"))
      (node (ref "P6") (pin "1") (pinfunction "1_1") (pintype "passive"))
      (node (ref "P6") (pin "2") (pinfunction "2_2") (pintype "passive"))
      (node (ref "P6") (pin "3") (pinfunction "3_3") (pintype "passive"))
      (node (ref "P6") (pin "4") (pinfunction "4_4") (pintype "passive"))
      (node (ref "P6") (pin "5") (pinfunction "5_5") (pintype "passive"))
      (node (ref "P6") (pin "6") (pinfunction "6_6") (pintype "passive"))
      (node (ref "P9") (pin "1") (pinfunction "1_1") (pintype "passive"))
      (node (ref "P9") (pin "2") (pinfunction "2_2") (pintype "passive"))
      (node (ref "P9") (pin "3") (pinfunction "3_3") (pintype "passive"))
      (node (ref "P9") (pin "4") (pinfunction "4_4") (pintype "passive"))
      (node (ref "P9") (pin "5") (pinfunction "5_5") (pintype "passive"))
      (node (ref "P9") (pin "6") (pinfunction "6_6") (pintype "passive"))
      (node (ref "R3") (pin "1") (pinfunction "1_1") (pintype "passive"))
      (node (ref "U*") (pin "GND@1") (pinfunction "GND@1_GND@1") (pintype "bidirectional"))
      (node (ref "U*") (pin "GND@2") (pinfunction "GND@2_GND@2") (pintype "bidirectional"))
      (node (ref "U*") (pin "GND@3") (pinfunction "GND@3_GND@3") (pintype "bidirectional"))
      (node (ref "U1") (pin "7") (pinfunction "0V_7") (pintype "passive"))
      (node (ref "U2") (pin "8") (pinfunction "GND_8") (pintype "input"))
      (node (ref "U3") (pin "8") (pinfunction "GND_8") (pintype "input"))
      (node (ref "U4") (pin "8") (pinfunction "GND_8") (pintype "input"))
    )
    (net (code "106") (name "GND") (class "Default")
      (node (ref "C1") (pin "1") (pinfunction "1_1") (pintype "passive"))
      (node (ref "C3") (pin "1") (pinfunction "1_1") (pintype "passive"))
      (node (ref "C4") (pin "1") (pinfunction "1_1") (pintype "passive"))
      (node (ref "C6") (pin "1") (pinfunction "1_1") (pintype "passive"))
      (node (ref "C7") (pin "2") (pinfunction "2_2") (pintype "passive"))
      (node (ref "C9") (pin "2") (pinfunction "2_2") (pintype "passive"))
      (node (ref "P10") (pin "1") (pinfunction "IO_1") (pintype "passive"))
      (node (ref "P11") (pin "1") (pinfunction "IO_1") (pintype "passive"))
      (node (ref "PS1") (pin "3") (pinfunction "C3_3") (pintype "passive"))
      (node (ref "PS1") (pin "4") (pinfunction "C4_4") (pintype "passive"))
      (node (ref "PS2") (pin "3") (pinfunction "C3_3") (pintype "passive"))
      (node (ref "PS2") (pin "4") (pinfunction "C4_4") (pintype "passive"))
      (node (ref "R1") (pin "1") (pinfunction "1_1") (pintype "passive"))
      (node (ref "R2") (pin "1") (pinfunction "1_1") (pintype "passive"))
      (node (ref "U1") (pin "1") (pinfunction "GND_1") (pintype "passive"))
    )
    (net (code "107") (name "Net-(D1-PadK)") (class "Default")
      (node (ref "D1") (pin "K") (pinfunction "K_K") (pintype "passive"))
      (node (ref "R1") (pin "2") (pinfunction "2_2") (pintype "passive"))
    )
    (net (code "108") (name "Net-(D2-PadK)") (class "Default")
      (node (ref "D2") (pin "K") (pinfunction "K_K") (pintype "passive"))
      (node (ref "R2") (pin "2") (pinfunction "2_2") (pintype "passive"))
    )
    (net (code "109") (name "Net-(D3-PadK)") (class "Default")
      (node (ref "D3") (pin "K") (pinfunction "K_K") (pintype "passive"))
      (node (ref "R3") (pin "2") (pinfunction "2_2") (pintype "passive"))
    )
    (net (code "110") (name "unconnected-(IC1-EXTCLK-Pad25)") (class "Default")
      (node (ref "IC1") (pin "25") (pinfunction "EXTCLK_25") (pintype "passive+no_connect"))
    )
    (net (code "111") (name "unconnected-(IC2-EXTCLK-Pad25)") (class "Default")
      (node (ref "IC2") (pin "25") (pinfunction "EXTCLK_25") (pintype "passive+no_connect"))
    )
    (net (code "112") (name "unconnected-(IC3-EXTCLK-Pad25)") (class "Default")
      (node (ref "IC3") (pin "25") (pinfunction "EXTCLK_25") (pintype "passive+no_connect"))
    )
    (net (code "113") (name "unconnected-(U*-Pad3V3@1)") (class "Default")
      (node (ref "U*") (pin "3V3@1") (pinfunction "3V3@1_3V3@1") (pintype "bidirectional"))
    )
    (net (code "114") (name "unconnected-(U*-Pad3V3@2)") (class "Default")
      (node (ref "U*") (pin "3V3@2") (pinfunction "3V3@2_3V3@2") (pintype "bidirectional"))
    )
    (net (code "115") (name "unconnected-(U*-PadA2)") (class "Default")
      (node (ref "U*") (pin "A2") (pinfunction "A2_A2") (pintype "bidirectional"))
    )
    (net (code "116") (name "unconnected-(U*-PadA4)") (class "Default")
      (node (ref "U*") (pin "A4") (pinfunction "A4_A4") (pintype "bidirectional"))
    )
    (net (code "117") (name "unconnected-(U*-PadA5)") (class "Default")
      (node (ref "U*") (pin "A5") (pinfunction "A5_A5") (pintype "bidirectional"))
    )
    (net (code "118") (name "unconnected-(U*-PadA6)") (class "Default")
      (node (ref "U*") (pin "A6") (pinfunction "A6_A6") (pintype "bidirectional"))
    )
    (net (code "119") (name "unconnected-(U*-PadA7)") (class "Default")
      (node (ref "U*") (pin "A7") (pinfunction "A7_A7") (pintype "bidirectional"))
    )
    (net (code "120") (name "unconnected-(U*-PadA8)") (class "Default")
      (node (ref "U*") (pin "A8") (pinfunction "A8_A8") (pintype "bidirectional"))
    )
    (net (code "121") (name "unconnected-(U*-PadA9)") (class "Default")
      (node (ref "U*") (pin "A9") (pinfunction "A9_A9") (pintype "bidirectional"))
    )
    (net (code "122") (name "unconnected-(U*-PadA10)") (class "Default")
      (node (ref "U*") (pin "A10") (pinfunction "A10_A10") (pintype "bidirectional"))
    )
    (net (code "123") (name "unconnected-(U*-PadA11)") (class "Default")
      (node (ref "U*") (pin "A11") (pinfunction "A11_A11") (pintype "bidirectional"))
    )
    (net (code "124") (name "unconnected-(U*-PadA12)") (class "Default")
      (node (ref "U*") (pin "A12") (pinfunction "A12_A12") (pintype "bidirectional"))
    )
    (net (code "125") (name "unconnected-(U*-PadA13)") (class "Default")
      (node (ref "U*") (pin "A13") (pinfunction "A13_A13") (pintype "bidirectional"))
    )
    (net (code "126") (name "unconnected-(U*-PadA14)") (class "Default")
      (node (ref "U*") (pin "A14") (pinfunction "A14_A14") (pintype "bidirectional"))
    )
    (net (code "127") (name "unconnected-(U*-PadA15)") (class "Default")
      (node (ref "U*") (pin "A15") (pinfunction "A15_A15") (pintype "bidirectional"))
    )
    (net (code "128") (name "unconnected-(U*-PadAREF)") (class "Default")
      (node (ref "U*") (pin "AREF") (pinfunction "AREF_AREF") (pintype "bidirectional"))
    )
    (net (code "129") (name "unconnected-(U*-PadD2)") (class "Default")
      (node (ref "U*") (pin "D2") (pinfunction "D2_D2") (pintype "bidirectional"))
    )
    (net (code "130") (name "unconnected-(U*-PadD3)") (class "Default")
      (node (ref "U*") (pin "D3") (pinfunction "D3_D3") (pintype "bidirectional"))
    )
    (net (code "131") (name "unconnected-(U*-PadD4)") (class "Default")
      (node (ref "U*") (pin "D4") (pinfunction "D4_D4") (pintype "bidirectional"))
    )
    (net (code "132") (name "unconnected-(U*-PadD5)") (class "Default")
      (node (ref "U*") (pin "D5") (pinfunction "D5_D5") (pintype "bidirectional"))
    )
    (net (code "133") (name "unconnected-(U*-PadD6)") (class "Default")
      (node (ref "U*") (pin "D6") (pinfunction "D6_D6") (pintype "bidirectional"))
    )
    (net (code "134") (name "unconnected-(U*-PadD7)") (class "Default")
      (node (ref "U*") (pin "D7") (pinfunction "D7_D7") (pintype "bidirectional"))
    )
    (net (code "135") (name "unconnected-(U*-PadD8)") (class "Default")
      (node (ref "U*") (pin "D8") (pinfunction "D8_D8") (pintype "bidirectional"))
    )
    (net (code "136") (name "unconnected-(U*-PadD9)") (class "Default")
      (node (ref "U*") (pin "D9") (pinfunction "D9_D9") (pintype "bidirectional"))
    )
    (net (code "137") (name "unconnected-(U*-PadD10)") (class "Default")
      (node (ref "U*") (pin "D10") (pinfunction "D10_D10") (pintype "bidirectional"))
    )
    (net (code "138") (name "unconnected-(U*-PadD11)") (class "Default")
      (node (ref "U*") (pin "D11") (pinfunction "D11_D11") (pintype "bidirectional"))
    )
    (net (code "139") (name "unconnected-(U*-PadD12)") (class "Default")
      (node (ref "U*") (pin "D12") (pinfunction "D12_D12") (pintype "bidirectional"))
    )
    (net (code "140") (name "unconnected-(U*-PadD13)") (class "Default")
      (node (ref "U*") (pin "D13") (pinfunction "D13_D13") (pintype "bidirectional"))
    )
    (net (code "141") (name "unconnected-(U*-PadD14)") (class "Default")
      (node (ref "U*") (pin "D14") (pinfunction "D14_D14") (pintype "bidirectional"))
    )
    (net (code "142") (name "unconnected-(U*-PadD15)") (class "Default")
      (node (ref "U*") (pin "D15") (pinfunction "D15_D15") (pintype "bidirectional"))
    )
    (net (code "143") (name "unconnected-(U*-PadD16)") (class "Default")
      (node (ref "U*") (pin "D16") (pinfunction "D16_D16") (pintype "bidirectional"))
    )
    (net (code "144") (name "unconnected-(U*-PadD17)") (class "Default")
      (node (ref "U*") (pin "D17") (pinfunction "D17_D17") (pintype "bidirectional"))
    )
    (net (code "145") (name "unconnected-(U*-PadD18)") (class "Default")
      (node (ref "U*") (pin "D18") (pinfunction "D18_D18") (pintype "bidirectional"))
    )
    (net (code "146") (name "unconnected-(U*-PadD19)") (class "Default")
      (node (ref "U*") (pin "D19") (pinfunction "D19_D19") (pintype "bidirectional"))
    )
    (net (code "147") (name "unconnected-(U*-PadD22)") (class "Default")
      (node (ref "U*") (pin "D22") (pinfunction "D22_D22") (pintype "bidirectional"))
    )
    (net (code "148") (name "unconnected-(U*-PadD23)") (class "Default")
      (node (ref "U*") (pin "D23") (pinfunction "D23_D23") (pintype "bidirectional"))
    )
    (net (code "149") (name "unconnected-(U*-PadD24)") (class "Default")
      (node (ref "U*") (pin "D24") (pinfunction "D24_D24") (pintype "bidirectional"))
    )
    (net (code "150") (name "unconnected-(U*-PadD25)") (class "Default")
      (node (ref "U*") (pin "D25") (pinfunction "D25_D25") (pintype "bidirectional"))
    )
    (net (code "151") (name "unconnected-(U*-PadD26)") (class "Default")
      (node (ref "U*") (pin "D26") (pinfunction "D26_D26") (pintype "bidirectional"))
    )
    (net (code "152") (name "unconnected-(U*-PadD27)") (class "Default")
      (node (ref "U*") (pin "D27") (pinfunction "D27_D27") (pintype "bidirectional"))
    )
    (net (code "153") (name "unconnected-(U*-PadD28)") (class "Default")
      (node (ref "U*") (pin "D28") (pinfunction "D28_D28") (pintype "bidirectional"))
    )
    (net (code "154") (name "unconnected-(U*-PadD29)") (class "Default")
      (node (ref "U*") (pin "D29") (pinfunction "D29_D29") (pintype "bidirectional"))
    )
    (net (code "155") (name "unconnected-(U*-PadD30)") (class "Default")
      (node (ref "U*") (pin "D30") (pinfunction "D30_D30") (pintype "bidirectional"))
    )
    (net (code "156") (name "unconnected-(U*-PadD31)") (class "Default")
      (node (ref "U*") (pin "D31") (pinfunction "D31_D31") (pintype "bidirectional"))
    )
    (net (code "157") (name "unconnected-(U*-PadD32)") (class "Default")
      (node (ref "U*") (pin "D32") (pinfunction "D32_D32") (pintype "bidirectional"))
    )
    (net (code "158") (name "unconnected-(U*-PadD33)") (class "Default")
      (node (ref "U*") (pin "D33") (pinfunction "D33_D33") (pintype "bidirectional"))
    )
    (net (code "159") (name "unconnected-(U*-PadD34)") (class "Default")
      (node (ref "U*") (pin "D34") (pinfunction "D34_D34") (pintype "bidirectional"))
    )
    (net (code "160") (name "unconnected-(U*-PadD35)") (class "Default")
      (node (ref "U*") (pin "D35") (pinfunction "D35_D35") (pintype "bidirectional"))
    )
    (net (code "161") (name "unconnected-(U*-PadD36)") (class "Default")
      (node (ref "U*") (pin "D36") (pinfunction "D36_D36") (pintype "bidirectional"))
    )
    (net (code "162") (name "unconnected-(U*-PadD37)") (class "Default")
      (node (ref "U*") (pin "D37") (pinfunction "D37_D37") (pintype "bidirectional"))
    )
    (net (code "163") (name "unconnected-(U*-PadD44)") (class "Default")
      (node (ref "U*") (pin "D44") (pinfunction "D44_D44") (pintype "bidirectional"))
    )
    (net (code "164") (name "unconnected-(U*-PadD45)") (class "Default")
      (node (ref "U*") (pin "D45") (pinfunction "D45_D45") (pintype "bidirectional"))
    )
    (net (code "165") (name "unconnected-(U*-PadD46)") (class "Default")
      (node (ref "U*") (pin "D46") (pinfunction "D46_D46") (pintype "bidirectional"))
    )
    (net (code "166") (name "unconnected-(U*-PadD47)") (class "Default")
      (node (ref "U*") (pin "D47") (pinfunction "D47_D47") (pintype "bidirectional"))
    )
    (net (code "167") (name "unconnected-(U*-PadD48)") (class "Default")
      (node (ref "U*") (pin "D48") (pinfunction "D48_D48") (pintype "bidirectional"))
    )
    (net (code "168") (name "unconnected-(U*-PadD49)") (class "Default")
      (node (ref "U*") (pin "D49") (pinfunction "D49_D49") (pintype "bidirectional"))
    )
    (net (code "169") (name "unconnected-(U*-PadD50)") (class "Default")
      (node (ref "U*") (pin "D50") (pinfunction "D50_D50") (pintype "bidirectional"))
    )
    (net (code "170") (name "unconnected-(U*-PadD51)") (class "Default")
      (node (ref "U*") (pin "D51") (pinfunction "D51_D51") (pintype "bidirectional"))
    )
    (net (code "171") (name "unconnected-(U*-PadD52)") (class "Default")
      (node (ref "U*") (pin "D52") (pinfunction "D52_D52") (pintype "bidirectional"))
    )
    (net (code "172") (name "unconnected-(U*-PadD53)") (class "Default")
      (node (ref "U*") (pin "D53") (pinfunction "D53_D53") (pintype "bidirectional"))
    )
    (net (code "173") (name "unconnected-(U*-PadMISO)") (class "Default")
      (node (ref "U*") (pin "MISO") (pinfunction "MISO_MISO") (pintype "bidirectional"))
    )
    (net (code "174") (name "unconnected-(U*-PadMOSI)") (class "Default")
      (node (ref "U*") (pin "MOSI") (pinfunction "MOSI_MOSI") (pintype "bidirectional"))
    )
    (net (code "175") (name "unconnected-(U*-PadRESET)") (class "Default")
      (node (ref "U*") (pin "RESET") (pinfunction "RESET_RESET") (pintype "bidirectional"))
    )
    (net (code "176") (name "unconnected-(U*-PadRST)") (class "Default")
      (node (ref "U*") (pin "RST") (pinfunction "RST_RST") (pintype "bidirectional"))
    )
    (net (code "177") (name "unconnected-(U*-PadRX)") (class "Default")
      (node (ref "U*") (pin "RX") (pinfunction "RX_RX") (pintype "bidirectional"))
    )
    (net (code "178") (name "unconnected-(U*-PadSCK)") (class "Default")
      (node (ref "U*") (pin "SCK") (pinfunction "SCK_SCK") (pintype "bidirectional"))
    )
    (net (code "179") (name "unconnected-(U*-PadTX)") (class "Default")
      (node (ref "U*") (pin "TX") (pinfunction "TX_TX") (pintype "bidirectional"))
    )
    (net (code "180") (name "unconnected-(U*-PadVIN@1)") (class "Default")
      (node (ref "U*") (pin "VIN@1") (pinfunction "VIN@1_VIN@1") (pintype "bidirectional"))
    )
    (net (code "181") (name "unconnected-(U*-PadVIN@2)") (class "Default")
      (node (ref "U*") (pin "VIN@2") (pinfunction "VIN@2_VIN@2") (pintype "bidirectional"))
    )
    (net (code "182") (name "unconnected-(U1-Ctrl-Pad3)") (class "Default")
      (node (ref "U1") (pin "3") (pinfunction "Ctrl_3") (pintype "passive+no_connect"))
    )
    (net (code "183") (name "unconnected-(U1-NC-Pad5)") (class "Default")
      (node (ref "U1") (pin "5") (pinfunction "NC_5") (pintype "passive"))
    )
    (net (code "184") (name "unconnected-(U1-NC-Pad8)") (class "Default")
      (node (ref "U1") (pin "8") (pinfunction "NC_8") (pintype "passive"))
    )
  )
)
